# e_book_reader.net
KiCad netlist of a schematic drawn in EAGLE
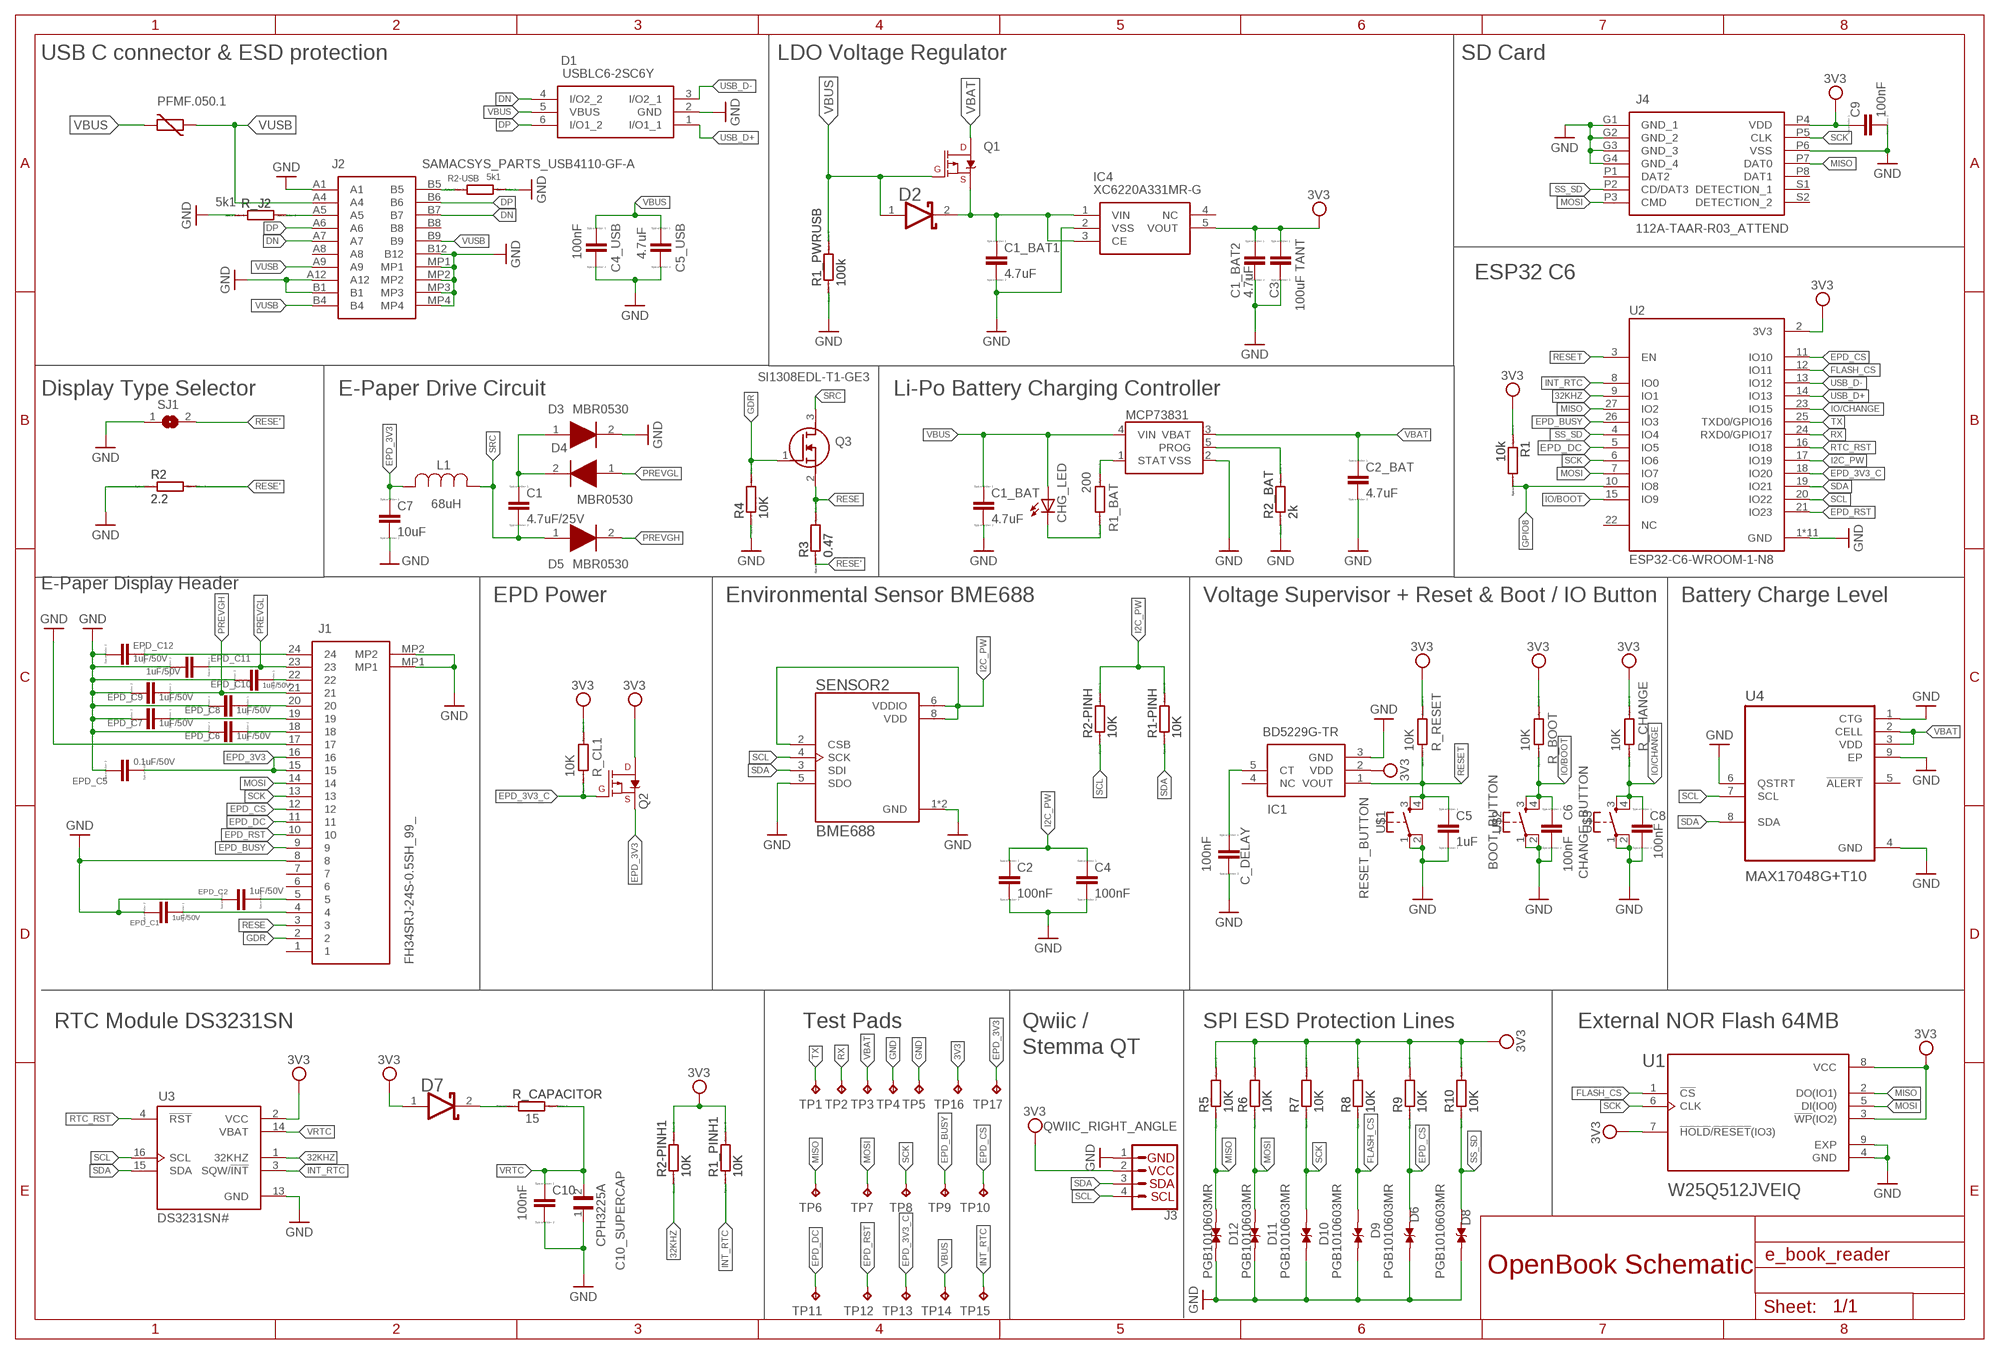
[diagram p0: schematic, sheet 1]

(export (version "E")
  (design (tool "Eeschema 10.0.6"))
  (components
    (comp (ref "C1")
      (value "4.7uF/25V")
      (footprint "eagle-import:ESP32_WROVER_EAGLE-LTSPICE_C0402")
      (libsource (lib "eagle-import") (part "ESP32_WROVER_EAGLE-LTSPICE_C"))
    )
    (comp (ref "C1_BAT")
      (value "4.7uF")
      (footprint "eagle-import:ESP32_WROVER_EAGLE-LTSPICE_C0402")
      (libsource (lib "eagle-import") (part "ESP32_WROVER_EAGLE-LTSPICE_C"))
    )
    (comp (ref "C1_BAT1")
      (value "4.7uF")
      (footprint "eagle-import:ESP32_WROVER_EAGLE-LTSPICE_C0402")
      (libsource (lib "eagle-import") (part "ESP32_WROVER_EAGLE-LTSPICE_C"))
    )
    (comp (ref "C1_BAT2")
      (value "4.7uF")
      (footprint "eagle-import:ESP32_WROVER_EAGLE-LTSPICE_C0402")
      (libsource (lib "eagle-import") (part "ESP32_WROVER_EAGLE-LTSPICE_C"))
    )
    (comp (ref "C2")
      (value "100nF")
      (footprint "eagle-import:ESP32_WROVER_EAGLE-LTSPICE_C0402")
      (libsource (lib "eagle-import") (part "ESP32_WROVER_EAGLE-LTSPICE_C"))
    )
    (comp (ref "C2_BAT")
      (value "4.7uF")
      (footprint "eagle-import:ESP32_WROVER_EAGLE-LTSPICE_C0402")
      (libsource (lib "eagle-import") (part "ESP32_WROVER_EAGLE-LTSPICE_C"))
    )
    (comp (ref "C3")
      (value "100uF TANT")
      (footprint "eagle-import:ESP32_WROVER_EAGLE-LTSPICE_C0402")
      (libsource (lib "eagle-import") (part "ESP32_WROVER_EAGLE-LTSPICE_C"))
    )
    (comp (ref "C4")
      (value "100nF")
      (footprint "eagle-import:ESP32_WROVER_EAGLE-LTSPICE_C0402")
      (libsource (lib "eagle-import") (part "ESP32_WROVER_EAGLE-LTSPICE_C"))
    )
    (comp (ref "C4_USB")
      (value "100nF")
      (footprint "eagle-import:ESP32_WROVER_EAGLE-LTSPICE_C0402")
      (libsource (lib "eagle-import") (part "ESP32_WROVER_EAGLE-LTSPICE_C"))
    )
    (comp (ref "C5")
      (value "1uF")
      (footprint "eagle-import:EAGLE-LTSPICE_C0402")
      (libsource (lib "eagle-import") (part "EAGLE-LTSPICE_CC0402"))
    )
    (comp (ref "C5_USB")
      (value "4.7uF")
      (footprint "eagle-import:ESP32_WROVER_EAGLE-LTSPICE_C0402")
      (libsource (lib "eagle-import") (part "ESP32_WROVER_EAGLE-LTSPICE_C"))
    )
    (comp (ref "C6")
      (value "100nF")
      (footprint "eagle-import:EAGLE-LTSPICE_C0402")
      (libsource (lib "eagle-import") (part "EAGLE-LTSPICE_CC0402"))
    )
    (comp (ref "C7")
      (value "10uF")
      (footprint "eagle-import:ESP32_WROVER_EAGLE-LTSPICE_C0402")
      (libsource (lib "eagle-import") (part "ESP32_WROVER_EAGLE-LTSPICE_C"))
    )
    (comp (ref "C8")
      (value "100nF")
      (footprint "eagle-import:ESP32_WROVER_EAGLE-LTSPICE_C0402")
      (libsource (lib "eagle-import") (part "ESP32_WROVER_EAGLE-LTSPICE_C"))
    )
    (comp (ref "C9")
      (value "100nF")
      (footprint "eagle-import:ESP32_WROVER_EAGLE-LTSPICE_C0402")
      (libsource (lib "eagle-import") (part "ESP32_WROVER_EAGLE-LTSPICE_C"))
    )
    (comp (ref "C10")
      (value "100nF")
      (footprint "eagle-import:ESP32_WROVER_EAGLE-LTSPICE_C0402")
      (libsource (lib "eagle-import") (part "ESP32_WROVER_EAGLE-LTSPICE_C"))
    )
    (comp (ref "C10_SUPERCAP")
      (value "CPH3225A")
      (footprint "eagle-import:CAPCP3225X100N")
      (fields (field (name "MF") "Seiko Instruments"))
      (libsource (lib "eagle-import") (part "CPH3225A"))
    )
    (comp (ref "CHG_LED")
      (value "ADAFRUIT_LEDCHIP-LED0603")
      (footprint "eagle-import:ADAFRUIT_CHIP-LED0603")
      (libsource (lib "eagle-import") (part "ADAFRUIT_LEDCHIP-LED0603"))
    )
    (comp (ref "C_DELAY")
      (value "100nF")
      (footprint "eagle-import:ESP32_WROVER_EAGLE-LTSPICE_C0402")
      (libsource (lib "eagle-import") (part "ESP32_WROVER_EAGLE-LTSPICE_C"))
    )
    (comp (ref "D1")
      (value "USBLC6-2SC6Y")
      (footprint "eagle-import:SOT95P280X145-6N")
      (fields (field (name "MF") "STMicroelectronics"))
      (libsource (lib "eagle-import") (part "USBLC6-2SC6Y"))
    )
    (comp (ref "D2")
      (value "ESP32_WROVER_AVX---SD0805S020S1R0_AVX_SD0805S020S1R0_0_0")
      (footprint "eagle-import:ESP32_WROVER_AVX---SD0805S020S1R0_AVX_SD0805S020S1R0_0")
      (libsource (lib "eagle-import") (part "ESP32_WROVER_AVX---SD0805S020S1R0_AVX_SD0805S020S1R0_0_0"))
    )
    (comp (ref "D3")
      (value "MBR0530")
      (footprint "eagle-import:SOD3716X135N")
      (libsource (lib "eagle-import") (part "MBR0530MY_MBR"))
    )
    (comp (ref "D4")
      (value "MBR0530")
      (footprint "eagle-import:SOD3716X135N")
      (libsource (lib "eagle-import") (part "MBR0530MY_MBR"))
    )
    (comp (ref "D5")
      (value "MBR0530")
      (footprint "eagle-import:SOD3716X135N")
      (libsource (lib "eagle-import") (part "MBR0530MY_MBR"))
    )
    (comp (ref "D6")
      (value "PGB1010603MR")
      (footprint "eagle-import:DIOC1608X36N")
      (libsource (lib "eagle-import") (part "PGB1010603MRPGB1010603MR"))
    )
    (comp (ref "D7")
      (value "ESP32_WROVER_AVX---SD0805S020S1R0_AVX_SD0805S020S1R0_0_0")
      (footprint "eagle-import:ESP32_WROVER_AVX---SD0805S020S1R0_AVX_SD0805S020S1R0_0")
      (libsource (lib "eagle-import") (part "ESP32_WROVER_AVX---SD0805S020S1R0_AVX_SD0805S020S1R0_0_0"))
    )
    (comp (ref "D8")
      (value "PGB1010603MR")
      (footprint "eagle-import:DIOC1608X36N")
      (libsource (lib "eagle-import") (part "PGB1010603MRPGB1010603MR"))
    )
    (comp (ref "D9")
      (value "PGB1010603MR")
      (footprint "eagle-import:DIOC1608X36N")
      (libsource (lib "eagle-import") (part "PGB1010603MRPGB1010603MR"))
    )
    (comp (ref "D10")
      (value "PGB1010603MR")
      (footprint "eagle-import:DIOC1608X36N")
      (libsource (lib "eagle-import") (part "PGB1010603MRPGB1010603MR"))
    )
    (comp (ref "D11")
      (value "PGB1010603MR")
      (footprint "eagle-import:DIOC1608X36N")
      (libsource (lib "eagle-import") (part "PGB1010603MRPGB1010603MR"))
    )
    (comp (ref "D12")
      (value "PGB1010603MR")
      (footprint "eagle-import:DIOC1608X36N")
      (libsource (lib "eagle-import") (part "PGB1010603MRPGB1010603MR"))
    )
    (comp (ref "EPD_C1")
      (value "1uF/50V")
      (footprint "eagle-import:ESP32_WROVER_EAGLE-LTSPICE_C0402")
      (libsource (lib "eagle-import") (part "ESP32_WROVER_EAGLE-LTSPICE_C"))
    )
    (comp (ref "EPD_C2")
      (value "1uF/50V")
      (footprint "eagle-import:ESP32_WROVER_EAGLE-LTSPICE_C0402")
      (libsource (lib "eagle-import") (part "ESP32_WROVER_EAGLE-LTSPICE_C"))
    )
    (comp (ref "EPD_C5")
      (value "0.1uF/50V")
      (footprint "eagle-import:ESP32_WROVER_EAGLE-LTSPICE_C0402")
      (libsource (lib "eagle-import") (part "ESP32_WROVER_EAGLE-LTSPICE_C"))
    )
    (comp (ref "EPD_C6")
      (value "1uF/50V")
      (footprint "eagle-import:ESP32_WROVER_EAGLE-LTSPICE_C0402")
      (libsource (lib "eagle-import") (part "ESP32_WROVER_EAGLE-LTSPICE_C"))
    )
    (comp (ref "EPD_C7")
      (value "1uF/50V")
      (footprint "eagle-import:ESP32_WROVER_EAGLE-LTSPICE_C0402")
      (libsource (lib "eagle-import") (part "ESP32_WROVER_EAGLE-LTSPICE_C"))
    )
    (comp (ref "EPD_C8")
      (value "1uF/50V")
      (footprint "eagle-import:ESP32_WROVER_EAGLE-LTSPICE_C0402")
      (libsource (lib "eagle-import") (part "ESP32_WROVER_EAGLE-LTSPICE_C"))
    )
    (comp (ref "EPD_C9")
      (value "1uF/50V")
      (footprint "eagle-import:ESP32_WROVER_EAGLE-LTSPICE_C0402")
      (libsource (lib "eagle-import") (part "ESP32_WROVER_EAGLE-LTSPICE_C"))
    )
    (comp (ref "EPD_C10")
      (value "1uF/50V")
      (footprint "eagle-import:ESP32_WROVER_EAGLE-LTSPICE_C0402")
      (libsource (lib "eagle-import") (part "ESP32_WROVER_EAGLE-LTSPICE_C"))
    )
    (comp (ref "EPD_C11")
      (value "1uF/50V")
      (footprint "eagle-import:ESP32_WROVER_EAGLE-LTSPICE_C0402")
      (libsource (lib "eagle-import") (part "ESP32_WROVER_EAGLE-LTSPICE_C"))
    )
    (comp (ref "EPD_C12")
      (value "1uF/50V")
      (footprint "eagle-import:ESP32_WROVER_EAGLE-LTSPICE_C0402")
      (libsource (lib "eagle-import") (part "ESP32_WROVER_EAGLE-LTSPICE_C"))
    )
    (comp (ref "IC1")
      (value "BD5229G-TR")
      (footprint "eagle-import:SOT95P280X125-5N")
      (fields (field (name "MOUSER_PART_NUMBER") "755-BD5229G-TR"))
      (libsource (lib "eagle-import") (part "BD5229G-TR"))
    )
    (comp (ref "IC4")
      (value "XC6220A331MR-G")
      (footprint "eagle-import:SOT95P280X120-5N")
      (fields (field (name "MOUSER_PART_NUMBER") "865-XC6220A331MR-G"))
      (libsource (lib "eagle-import") (part "XC6220A331MR-G"))
    )
    (comp (ref "J1")
      (value "FH34SRJ-24S-0.5SH_99_")
      (footprint "eagle-import:FH34SRJ24S05SH99")
      (fields
        (field (name "MANUFACTURER_PART_NUMBER") "FH34SRJ-24S-0.5SH(99)")
        (field (name "MOUSER_PART_NUMBER") "798-FH34SRJ24S05SH99")
      )
      (libsource (lib "eagle-import") (part "FH34SRJ-24S-0.5SH_99_"))
    )
    (comp (ref "J2")
      (value "SAMACSYS_PARTS_USB4110-GF-A")
      (footprint "eagle-import:SAMACSYS_PARTS_USB4110GFA")
      (fields
        (field (name "MANUFACTURER_PART_NUMBER") "USB4110-GF-A")
        (field (name "MOUSER_PART_NUMBER") "640-USB4110-GF-A")
      )
      (libsource (lib "eagle-import") (part "SAMACSYS_PARTS_USB4110-GF-A"))
    )
    (comp (ref "J3")
      (value "QWIIC_RIGHT_ANGLE")
      (footprint "eagle-import:JST04_1MM_RA")
      (libsource (lib "eagle-import") (part "QWIIC_CONNECTORJS-1MM"))
    )
    (comp (ref "J4")
      (value "112A-TAAR-R03_ATTEND")
      (footprint "eagle-import:112ATAARR03ATTEND")
      (fields (field (name "MANUFACTURER_PART_NUMBER") "112A-TAAR-R03 ATTEND"))
      (libsource (lib "eagle-import") (part "112A-TAAR-R03_ATTEND"))
    )
    (comp (ref "L1")
      (value "68uH")
      (footprint "eagle-import:IND_4828-WE-TPC_WRE")
      (fields
        (field (name "MANUFACTURER_PART_NUMBER") "744043680")
        (field (name "COPYRIGHT") "Copyright (C) 2024 Ultra Librarian. All rights reserved.")
      )
      (libsource (lib "eagle-import") (part "744043680IND_4828-WE-TPC_WRE"))
    )
    (comp (ref "MCP73831")
      (value "ESP32_WROVER_SPARKFUN-IC-POWER_MCP73831")
      (footprint "eagle-import:ESP32_WROVER_SPARKFUN-IC-POWER_SOT23-5")
      (libsource (lib "eagle-import") (part "ESP32_WROVER_SPARKFUN-IC-POWER_MCP73831"))
    )
    (comp (ref "PFMF.050.1")
      (value "ESP32C6_VARISTORCN1812")
      (footprint "eagle-import:ESP32C6_VARISTOR_CT_CN1812")
      (libsource (lib "eagle-import") (part "ESP32C6_VARISTORCN1812"))
    )
    (comp (ref "Q1")
      (value "ESP32_WROVER_SPARKFUN-DISCRETESEMI_MOSFET_PCH")
      (footprint "eagle-import:ESP32_WROVER_SPARKFUN-DISCRETESEMI_SOT23-3")
      (libsource (lib "eagle-import") (part "ESP32_WROVER_SPARKFUN-DISCRETESEMI_MOSFET_PCH"))
    )
    (comp (ref "Q2")
      (value "ESP32_WROVER_SPARKFUN-DISCRETESEMI_MOSFET_PCH")
      (footprint "eagle-import:ESP32_WROVER_SPARKFUN-DISCRETESEMI_SOT23-3")
      (libsource (lib "eagle-import") (part "ESP32_WROVER_SPARKFUN-DISCRETESEMI_MOSFET_PCH"))
    )
    (comp (ref "Q3")
      (value "SI1308EDL-T1-GE3")
      (footprint "eagle-import:SOT65P210X110-3N")
      (fields (field (name "MF") "Vishay Siliconix"))
      (libsource (lib "eagle-import") (part "SI1308EDL-T1-GE3"))
    )
    (comp (ref "R1")
      (value "10k")
      (footprint "eagle-import:ESP32_WROVER_EAGLE-LTSPICE_R0402")
      (libsource (lib "eagle-import") (part "ESP32_WROVER_EAGLE-LTSPICE_R"))
    )
    (comp (ref "R1-PINH")
      (value "10K")
      (footprint "eagle-import:ESP32_WROVER_EAGLE-LTSPICE_R0402")
      (libsource (lib "eagle-import") (part "ESP32_WROVER_EAGLE-LTSPICE_R"))
    )
    (comp (ref "R1_BAT")
      (value "200")
      (footprint "eagle-import:ESP32_WROVER_EAGLE-LTSPICE_R0402")
      (libsource (lib "eagle-import") (part "ESP32_WROVER_EAGLE-LTSPICE_R"))
    )
    (comp (ref "R1_PINH1")
      (value "10K")
      (footprint "eagle-import:ESP32_WROVER_EAGLE-LTSPICE_R0402")
      (libsource (lib "eagle-import") (part "ESP32_WROVER_EAGLE-LTSPICE_R"))
    )
    (comp (ref "R1_PWRUSB")
      (value "100k")
      (footprint "eagle-import:ESP32_WROVER_EAGLE-LTSPICE_R0402")
      (libsource (lib "eagle-import") (part "ESP32_WROVER_EAGLE-LTSPICE_R"))
    )
    (comp (ref "R2")
      (value "2.2")
      (footprint "eagle-import:ESP32_WROVER_EAGLE-LTSPICE_R0402")
      (libsource (lib "eagle-import") (part "ESP32_WROVER_EAGLE-LTSPICE_R"))
    )
    (comp (ref "R2-PINH")
      (value "10K")
      (footprint "eagle-import:ESP32_WROVER_EAGLE-LTSPICE_R0402")
      (libsource (lib "eagle-import") (part "ESP32_WROVER_EAGLE-LTSPICE_R"))
    )
    (comp (ref "R2-PINH1")
      (value "10K")
      (footprint "eagle-import:ESP32_WROVER_EAGLE-LTSPICE_R0402")
      (libsource (lib "eagle-import") (part "ESP32_WROVER_EAGLE-LTSPICE_R"))
    )
    (comp (ref "R2-USB")
      (value "5k1")
      (footprint "eagle-import:ESP32_WROVER_EAGLE-LTSPICE_R0402")
      (libsource (lib "eagle-import") (part "ESP32_WROVER_EAGLE-LTSPICE_R"))
    )
    (comp (ref "R2_BAT")
      (value "2k")
      (footprint "eagle-import:ESP32_WROVER_EAGLE-LTSPICE_R0402")
      (libsource (lib "eagle-import") (part "ESP32_WROVER_EAGLE-LTSPICE_R"))
    )
    (comp (ref "R3")
      (value "0.47")
      (footprint "eagle-import:ESP32_WROVER_EAGLE-LTSPICE_R0402")
      (libsource (lib "eagle-import") (part "ESP32_WROVER_EAGLE-LTSPICE_R"))
    )
    (comp (ref "R4")
      (value "10K")
      (footprint "eagle-import:ESP32_WROVER_EAGLE-LTSPICE_R0402")
      (libsource (lib "eagle-import") (part "ESP32_WROVER_EAGLE-LTSPICE_R"))
    )
    (comp (ref "R5")
      (value "10K")
      (footprint "eagle-import:ESP32_WROVER_EAGLE-LTSPICE_R0402")
      (libsource (lib "eagle-import") (part "ESP32_WROVER_EAGLE-LTSPICE_R"))
    )
    (comp (ref "R6")
      (value "10K")
      (footprint "eagle-import:ESP32_WROVER_EAGLE-LTSPICE_R0402")
      (libsource (lib "eagle-import") (part "ESP32_WROVER_EAGLE-LTSPICE_R"))
    )
    (comp (ref "R7")
      (value "10K")
      (footprint "eagle-import:ESP32_WROVER_EAGLE-LTSPICE_R0402")
      (libsource (lib "eagle-import") (part "ESP32_WROVER_EAGLE-LTSPICE_R"))
    )
    (comp (ref "R8")
      (value "10K")
      (footprint "eagle-import:ESP32_WROVER_EAGLE-LTSPICE_R0402")
      (libsource (lib "eagle-import") (part "ESP32_WROVER_EAGLE-LTSPICE_R"))
    )
    (comp (ref "R9")
      (value "10K")
      (footprint "eagle-import:ESP32_WROVER_EAGLE-LTSPICE_R0402")
      (libsource (lib "eagle-import") (part "ESP32_WROVER_EAGLE-LTSPICE_R"))
    )
    (comp (ref "R10")
      (value "10K")
      (footprint "eagle-import:ESP32_WROVER_EAGLE-LTSPICE_R0402")
      (libsource (lib "eagle-import") (part "ESP32_WROVER_EAGLE-LTSPICE_R"))
    )
    (comp (ref "R_BOOT")
      (value "10K")
      (footprint "eagle-import:ESP32_WROVER_EAGLE-LTSPICE_R0402")
      (libsource (lib "eagle-import") (part "ESP32_WROVER_EAGLE-LTSPICE_R"))
    )
    (comp (ref "R_CAPACITOR")
      (value "15")
      (footprint "eagle-import:ESP32_WROVER_EAGLE-LTSPICE_R0402")
      (libsource (lib "eagle-import") (part "ESP32_WROVER_EAGLE-LTSPICE_R"))
    )
    (comp (ref "R_CHANGE")
      (value "10K")
      (footprint "eagle-import:ESP32_WROVER_EAGLE-LTSPICE_R0402")
      (libsource (lib "eagle-import") (part "ESP32_WROVER_EAGLE-LTSPICE_R"))
    )
    (comp (ref "R_CL1")
      (value "10K")
      (footprint "eagle-import:ESP32_WROVER_EAGLE-LTSPICE_R0402")
      (libsource (lib "eagle-import") (part "ESP32_WROVER_EAGLE-LTSPICE_R"))
    )
    (comp (ref "R_J2")
      (value "5k1")
      (footprint "eagle-import:ESP32_WROVER_EAGLE-LTSPICE_R0402")
      (libsource (lib "eagle-import") (part "ESP32_WROVER_EAGLE-LTSPICE_R"))
    )
    (comp (ref "R_RESET")
      (value "10K")
      (footprint "eagle-import:ESP32_WROVER_EAGLE-LTSPICE_R0402")
      (libsource (lib "eagle-import") (part "ESP32_WROVER_EAGLE-LTSPICE_R"))
    )
    (comp (ref "SENSOR2")
      (value "BME688")
      (footprint "eagle-import:ESP32_WROVER_BME680_PSON80P300X300X100-8N")
      (fields (field (name "MF") "Bosch Sensortec") (field (name "MP") "BME680"))
      (libsource (lib "eagle-import") (part "ESP32_WROVER_BME680_BME680"))
    )
    (comp (ref "SJ1") (value "SJ") (footprint "eagle-import:SJ") (libsource (lib "eagle-import") (part "SJ")))
    (comp (ref "TP1")
      (value "TPTP20R")
      (footprint "eagle-import:TP20R")
      (libsource (lib "eagle-import") (part "TPTP20R"))
    )
    (comp (ref "TP2")
      (value "TPTP20R")
      (footprint "eagle-import:TP20R")
      (libsource (lib "eagle-import") (part "TPTP20R"))
    )
    (comp (ref "TP3")
      (value "TPTP20R")
      (footprint "eagle-import:TP20R")
      (libsource (lib "eagle-import") (part "TPTP20R"))
    )
    (comp (ref "TP4")
      (value "TPTP20R")
      (footprint "eagle-import:TP20R")
      (libsource (lib "eagle-import") (part "TPTP20R"))
    )
    (comp (ref "TP5")
      (value "TPTP20R")
      (footprint "eagle-import:TP20R")
      (libsource (lib "eagle-import") (part "TPTP20R"))
    )
    (comp (ref "TP6")
      (value "TPTP20R")
      (footprint "eagle-import:TP20R")
      (libsource (lib "eagle-import") (part "TPTP20R"))
    )
    (comp (ref "TP7")
      (value "TPTP20R")
      (footprint "eagle-import:TP20R")
      (libsource (lib "eagle-import") (part "TPTP20R"))
    )
    (comp (ref "TP8")
      (value "TPTP20R")
      (footprint "eagle-import:TP20R")
      (libsource (lib "eagle-import") (part "TPTP20R"))
    )
    (comp (ref "TP9")
      (value "TPTP20R")
      (footprint "eagle-import:TP20R")
      (libsource (lib "eagle-import") (part "TPTP20R"))
    )
    (comp (ref "TP10")
      (value "TPTP20R")
      (footprint "eagle-import:TP20R")
      (libsource (lib "eagle-import") (part "TPTP20R"))
    )
    (comp (ref "TP11")
      (value "TPTP20R")
      (footprint "eagle-import:TP20R")
      (libsource (lib "eagle-import") (part "TPTP20R"))
    )
    (comp (ref "TP12")
      (value "TPTP20R")
      (footprint "eagle-import:TP20R")
      (libsource (lib "eagle-import") (part "TPTP20R"))
    )
    (comp (ref "TP13")
      (value "TPTP20R")
      (footprint "eagle-import:TP20R")
      (libsource (lib "eagle-import") (part "TPTP20R"))
    )
    (comp (ref "TP14")
      (value "TPTP20R")
      (footprint "eagle-import:TP20R")
      (libsource (lib "eagle-import") (part "TPTP20R"))
    )
    (comp (ref "TP15")
      (value "TPTP20R")
      (footprint "eagle-import:TP20R")
      (libsource (lib "eagle-import") (part "TPTP20R"))
    )
    (comp (ref "TP16")
      (value "TPTP20R")
      (footprint "eagle-import:TP20R")
      (libsource (lib "eagle-import") (part "TPTP20R"))
    )
    (comp (ref "TP17")
      (value "TP")
      (footprint "eagle-import:TP20R")
      (libsource (lib "eagle-import") (part "TP"))
    )
    (comp (ref "U$1")
      (value "RESET_BUTTON")
      (footprint "eagle-import:MYBUTTON")
      (libsource (lib "eagle-import") (part "BUTTON_CUSYOMV12_MYBUTTON"))
    )
    (comp (ref "U$2")
      (value "BOOT_BUTTON")
      (footprint "eagle-import:MYBUTTON")
      (libsource (lib "eagle-import") (part "BUTTON_CUSYOMV12_MYBUTTON"))
    )
    (comp (ref "U$3")
      (value "CHANGE_BUTTON")
      (footprint "eagle-import:MYBUTTON")
      (libsource (lib "eagle-import") (part "BUTTON_CUSYOMV12_MYBUTTON"))
    )
    (comp (ref "U1")
      (value "W25Q512JVEIQ")
      (footprint "eagle-import:SON127P600X800X80-9N")
      (fields (field (name "MF") "Winbond Electronics"))
      (libsource (lib "eagle-import") (part "W25Q512JVEIQ"))
    )
    (comp (ref "U2")
      (value "ESP32-C6-WROOM-1-N8")
      (footprint "eagle-import:XCVR_ESP32-C6-WROOM-1-N8")
      (fields (field (name "MF") "Espressif Systems"))
      (libsource (lib "eagle-import") (part "ESP32-C6-WROOM-1-N8"))
    )
    (comp (ref "U3")
      (value "DS3231SN#")
      (footprint "eagle-import:SOIC127P1032X265-16N")
      (fields (field (name "MF") "Analog Devices"))
      (libsource (lib "eagle-import") (part "DS3231SN#"))
    )
    (comp (ref "U4")
      (value "MAX17048G+T10")
      (footprint "eagle-import:SON50P200X200X80-9N")
      (fields (field (name "MF") "Analog Devices"))
      (libsource (lib "eagle-import") (part "MAX17048G+T10"))
    )
  )
  (nets
    (net (code "1") (name "3V3") (class "Default")
      (node (ref "C1_BAT2") (pin "1") (pinfunction "1_1") (pintype "passive"))
      (node (ref "C3") (pin "1") (pinfunction "1_1") (pintype "passive"))
      (node (ref "C9") (pin "1") (pinfunction "1_1") (pintype "passive"))
      (node (ref "D7") (pin "1") (pinfunction "ANODE_1") (pintype "bidirectional"))
      (node (ref "IC1") (pin "2") (pinfunction "VDD_2") (pintype "bidirectional"))
      (node (ref "IC4") (pin "5") (pinfunction "VOUT_5") (pintype "bidirectional"))
      (node (ref "J3") (pin "2") (pinfunction "2_2") (pintype "power_in"))
      (node (ref "J4") (pin "P4") (pinfunction "VDD_P4") (pintype "bidirectional"))
      (node (ref "Q2") (pin "1") (pinfunction "D_1") (pintype "bidirectional"))
      (node (ref "R1") (pin "1") (pinfunction "1_1") (pintype "passive"))
      (node (ref "R10") (pin "2") (pinfunction "2_2") (pintype "passive"))
      (node (ref "R1_PINH1") (pin "2") (pinfunction "2_2") (pintype "passive"))
      (node (ref "R2-PINH1") (pin "2") (pinfunction "2_2") (pintype "passive"))
      (node (ref "R5") (pin "2") (pinfunction "2_2") (pintype "passive"))
      (node (ref "R6") (pin "2") (pinfunction "2_2") (pintype "passive"))
      (node (ref "R7") (pin "2") (pinfunction "2_2") (pintype "passive"))
      (node (ref "R8") (pin "2") (pinfunction "2_2") (pintype "passive"))
      (node (ref "R9") (pin "2") (pinfunction "2_2") (pintype "passive"))
      (node (ref "R_BOOT") (pin "2") (pinfunction "2_2") (pintype "passive"))
      (node (ref "R_CHANGE") (pin "2") (pinfunction "2_2") (pintype "passive"))
      (node (ref "R_CL1") (pin "2") (pinfunction "2_2") (pintype "passive"))
      (node (ref "R_RESET") (pin "2") (pinfunction "2_2") (pintype "passive"))
      (node (ref "TP16") (pin "TP") (pinfunction "TP_TP") (pintype "input"))
      (node (ref "U1") (pin "3") (pinfunction "~{WP}(IO2)_3") (pintype "bidirectional"))
      (node (ref "U1") (pin "7") (pinfunction "~{HOLD}/~{RESET}(IO3)_7") (pintype "bidirectional"))
      (node (ref "U1") (pin "8") (pinfunction "VCC_8") (pintype "power_in"))
      (node (ref "U2") (pin "2") (pinfunction "3V3_2") (pintype "power_in"))
      (node (ref "U3") (pin "2") (pinfunction "VCC_2") (pintype "power_in"))
    )
    (net (code "2") (name "32KHZ") (class "Default")
      (node (ref "R2-PINH1") (pin "1") (pinfunction "1_1") (pintype "passive"))
      (node (ref "U2") (pin "9") (pinfunction "IO1_9") (pintype "bidirectional"))
      (node (ref "U3") (pin "1") (pinfunction "32KHZ_1") (pintype "output"))
    )
    (net (code "3") (name "DN") (class "Default")
      (node (ref "D1") (pin "4") (pinfunction "I/O2_2_4") (pintype "bidirectional"))
      (node (ref "J2") (pin "A7") (pinfunction "A7_A7") (pintype "bidirectional"))
      (node (ref "J2") (pin "B7") (pinfunction "B7_B7") (pintype "bidirectional"))
    )
    (net (code "4") (name "DP") (class "Default")
      (node (ref "D1") (pin "6") (pinfunction "I/O1_2_6") (pintype "bidirectional"))
      (node (ref "J2") (pin "A6") (pinfunction "A6_A6") (pintype "bidirectional"))
      (node (ref "J2") (pin "B6") (pinfunction "B6_B6") (pintype "bidirectional"))
    )
    (net (code "5") (name "EPD_3V3") (class "Default")
      (node (ref "C7") (pin "1") (pinfunction "1_1") (pintype "passive"))
      (node (ref "EPD_C5") (pin "1") (pinfunction "1_1") (pintype "passive"))
      (node (ref "J1") (pin "15") (pinfunction "15_15") (pintype "bidirectional"))
      (node (ref "J1") (pin "16") (pinfunction "16_16") (pintype "bidirectional"))
      (node (ref "L1") (pin "2") (pinfunction "2_2") (pintype "passive"))
      (node (ref "Q2") (pin "3") (pinfunction "S_3") (pintype "bidirectional"))
      (node (ref "TP17") (pin "TP") (pinfunction "TP_TP") (pintype "input"))
    )
    (net (code "6") (name "EPD_3V3_C") (class "Default")
      (node (ref "Q2") (pin "2") (pinfunction "G_2") (pintype "bidirectional"))
      (node (ref "R_CL1") (pin "1") (pinfunction "1_1") (pintype "passive"))
      (node (ref "TP13") (pin "TP") (pinfunction "TP_TP") (pintype "input"))
      (node (ref "U2") (pin "18") (pinfunction "IO20_18") (pintype "bidirectional"))
    )
    (net (code "7") (name "EPD_BUSY") (class "Default")
      (node (ref "J1") (pin "9") (pinfunction "9_9") (pintype "bidirectional"))
      (node (ref "TP9") (pin "TP") (pinfunction "TP_TP") (pintype "input"))
      (node (ref "U2") (pin "26") (pinfunction "IO3_26") (pintype "bidirectional"))
    )
    (net (code "8") (name "EPD_CS") (class "Default")
      (node (ref "D6") (pin "1") (pinfunction "1_1") (pintype "passive"))
      (node (ref "J1") (pin "12") (pinfunction "12_12") (pintype "bidirectional"))
      (node (ref "R9") (pin "1") (pinfunction "1_1") (pintype "passive"))
      (node (ref "TP10") (pin "TP") (pinfunction "TP_TP") (pintype "input"))
      (node (ref "U2") (pin "11") (pinfunction "IO10_11") (pintype "bidirectional"))
    )
    (net (code "9") (name "EPD_DC") (class "Default")
      (node (ref "J1") (pin "11") (pinfunction "11_11") (pintype "bidirectional"))
      (node (ref "TP11") (pin "TP") (pinfunction "TP_TP") (pintype "input"))
      (node (ref "U2") (pin "5") (pinfunction "IO5_5") (pintype "bidirectional"))
    )
    (net (code "10") (name "EPD_RST") (class "Default")
      (node (ref "J1") (pin "10") (pinfunction "10_10") (pintype "bidirectional"))
      (node (ref "TP12") (pin "TP") (pinfunction "TP_TP") (pintype "input"))
      (node (ref "U2") (pin "21") (pinfunction "IO23_21") (pintype "bidirectional"))
    )
    (net (code "11") (name "FLASH_CS") (class "Default")
      (node (ref "D9") (pin "1") (pinfunction "1_1") (pintype "passive"))
      (node (ref "R8") (pin "1") (pinfunction "1_1") (pintype "passive"))
      (node (ref "U1") (pin "1") (pinfunction "~{CS}_1") (pintype "input"))
      (node (ref "U2") (pin "12") (pinfunction "IO11_12") (pintype "bidirectional"))
    )
    (net (code "12") (name "GDR") (class "Default")
      (node (ref "J1") (pin "2") (pinfunction "2_2") (pintype "bidirectional"))
      (node (ref "Q3") (pin "1") (pinfunction "G_1") (pintype "bidirectional"))
      (node (ref "R4") (pin "2") (pinfunction "2_2") (pintype "passive"))
    )
    (net (code "13") (name "GND") (class "Default")
      (node (ref "C10") (pin "2") (pinfunction "2_2") (pintype "passive"))
      (node (ref "C10_SUPERCAP") (pin "1") (pinfunction "1_1") (pintype "passive"))
      (node (ref "C1_BAT") (pin "2") (pinfunction "2_2") (pintype "passive"))
      (node (ref "C1_BAT1") (pin "2") (pinfunction "2_2") (pintype "passive"))
      (node (ref "C1_BAT2") (pin "2") (pinfunction "2_2") (pintype "passive"))
      (node (ref "C2") (pin "2") (pinfunction "2_2") (pintype "passive"))
      (node (ref "C2_BAT") (pin "2") (pinfunction "2_2") (pintype "passive"))
      (node (ref "C3") (pin "2") (pinfunction "2_2") (pintype "passive"))
      (node (ref "C4") (pin "2") (pinfunction "2_2") (pintype "passive"))
      (node (ref "C4_USB") (pin "2") (pinfunction "2_2") (pintype "passive"))
      (node (ref "C5") (pin "2") (pinfunction "2_2") (pintype "passive"))
      (node (ref "C5_USB") (pin "2") (pinfunction "2_2") (pintype "passive"))
      (node (ref "C6") (pin "2") (pinfunction "2_2") (pintype "passive"))
      (node (ref "C7") (pin "2") (pinfunction "2_2") (pintype "passive"))
      (node (ref "C8") (pin "2") (pinfunction "2_2") (pintype "passive"))
      (node (ref "C9") (pin "2") (pinfunction "2_2") (pintype "passive"))
      (node (ref "C_DELAY") (pin "2") (pinfunction "2_2") (pintype "passive"))
      (node (ref "D1") (pin "2") (pinfunction "GND_2") (pintype "bidirectional"))
      (node (ref "D10") (pin "2") (pinfunction "2_2") (pintype "passive"))
      (node (ref "D11") (pin "2") (pinfunction "2_2") (pintype "passive"))
      (node (ref "D12") (pin "2") (pinfunction "2_2") (pintype "passive"))
      (node (ref "D3") (pin "2") (pinfunction "K_2") (pintype "bidirectional"))
      (node (ref "D6") (pin "2") (pinfunction "2_2") (pintype "passive"))
      (node (ref "D8") (pin "2") (pinfunction "2_2") (pintype "passive"))
      (node (ref "D9") (pin "2") (pinfunction "2_2") (pintype "passive"))
      (node (ref "EPD_C1") (pin "2") (pinfunction "2_2") (pintype "passive"))
      (node (ref "EPD_C10") (pin "2") (pinfunction "2_2") (pintype "passive"))
      (node (ref "EPD_C11") (pin "2") (pinfunction "2_2") (pintype "passive"))
      (node (ref "EPD_C12") (pin "2") (pinfunction "2_2") (pintype "passive"))
      (node (ref "EPD_C2") (pin "2") (pinfunction "2_2") (pintype "passive"))
      (node (ref "EPD_C5") (pin "2") (pinfunction "2_2") (pintype "passive"))
      (node (ref "EPD_C6") (pin "2") (pinfunction "2_2") (pintype "passive"))
      (node (ref "EPD_C7") (pin "2") (pinfunction "2_2") (pintype "passive"))
      (node (ref "EPD_C8") (pin "2") (pinfunction "2_2") (pintype "passive"))
      (node (ref "EPD_C9") (pin "2") (pinfunction "2_2") (pintype "passive"))
      (node (ref "IC1") (pin "3") (pinfunction "GND_3") (pintype "bidirectional"))
      (node (ref "IC4") (pin "2") (pinfunction "VSS_2") (pintype "bidirectional"))
      (node (ref "J1") (pin "17") (pinfunction "17_17") (pintype "bidirectional"))
      (node (ref "J1") (pin "8") (pinfunction "8_8") (pintype "bidirectional"))
      (node (ref "J1") (pin "MP1") (pinfunction "MP1_MP1") (pintype "bidirectional"))
      (node (ref "J1") (pin "MP2") (pinfunction "MP2_MP2") (pintype "bidirectional"))
      (node (ref "J2") (pin "A1") (pinfunction "A1_A1") (pintype "bidirectional"))
      (node (ref "J2") (pin "A12") (pinfunction "A12_A12") (pintype "bidirectional"))
      (node (ref "J2") (pin "B1") (pinfunction "B1_B1") (pintype "bidirectional"))
      (node (ref "J2") (pin "B12") (pinfunction "B12_B12") (pintype "bidirectional"))
      (node (ref "J2") (pin "MP1") (pinfunction "MP1_MP1") (pintype "bidirectional"))
      (node (ref "J2") (pin "MP2") (pinfunction "MP2_MP2") (pintype "bidirectional"))
      (node (ref "J2") (pin "MP3") (pinfunction "MP3_MP3") (pintype "bidirectional"))
      (node (ref "J2") (pin "MP4") (pinfunction "MP4_MP4") (pintype "bidirectional"))
      (node (ref "J3") (pin "1") (pinfunction "1_1") (pintype "power_in"))
      (node (ref "J4") (pin "G1") (pinfunction "GND_1_G1") (pintype "bidirectional"))
      (node (ref "J4") (pin "G2") (pinfunction "GND_2_G2") (pintype "bidirectional"))
      (node (ref "J4") (pin "G3") (pinfunction "GND_3_G3") (pintype "bidirectional"))
      (node (ref "J4") (pin "G4") (pinfunction "GND_4_G4") (pintype "bidirectional"))
      (node (ref "J4") (pin "P6") (pinfunction "VSS_P6") (pintype "bidirectional"))
      (node (ref "MCP73831") (pin "2") (pinfunction "VSS_2") (pintype "power_in"))
      (node (ref "R1_PWRUSB") (pin "1") (pinfunction "1_1") (pintype "passive"))
      (node (ref "R2") (pin "1") (pinfunction "1_1") (pintype "passive"))
      (node (ref "R2-USB") (pin "2") (pinfunction "2_2") (pintype "passive"))
      (node (ref "R2_BAT") (pin "1") (pinfunction "1_1") (pintype "passive"))
      (node (ref "R4") (pin "1") (pinfunction "1_1") (pintype "passive"))
      (node (ref "R_J2") (pin "1") (pinfunction "1_1") (pintype "passive"))
      (node (ref "SENSOR2") (pin "1") (pinfunction "GND_1") (pintype "power_in"))
      (node (ref "SENSOR2") (pin "5") (pinfunction "SDO_5") (pintype "bidirectional"))
      (node (ref "SENSOR2") (pin "7") (pinfunction "GND_7") (pintype "power_in"))
      (node (ref "SJ1") (pin "1") (pinfunction "1_1") (pintype "passive"))
      (node (ref "TP4") (pin "TP") (pinfunction "TP_TP") (pintype "input"))
      (node (ref "TP5") (pin "TP") (pinfunction "TP_TP") (pintype "input"))
      (node (ref "U$1") (pin "1") (pinfunction "1_1") (pintype "passive"))
      (node (ref "U$1") (pin "2") (pinfunction "2_2") (pintype "passive"))
      (node (ref "U$2") (pin "1") (pinfunction "1_1") (pintype "passive"))
      (node (ref "U$2") (pin "2") (pinfunction "2_2") (pintype "passive"))
      (node (ref "U$3") (pin "1") (pinfunction "1_1") (pintype "passive"))
      (node (ref "U$3") (pin "2") (pinfunction "2_2") (pintype "passive"))
      (node (ref "U1") (pin "4") (pinfunction "GND_4") (pintype "power_in"))
      (node (ref "U1") (pin "9") (pinfunction "EXP_9") (pintype "passive"))
      (node (ref "U2") (pin "1") (pinfunction "GND_1") (pintype "power_in"))
      (node (ref "U2") (pin "28") (pinfunction "GND_28") (pintype "power_in"))
      (node (ref "U2") (pin "29_1") (pinfunction "GND_29_1") (pintype "power_in"))
      (node (ref "U2") (pin "29_2") (pinfunction "GND_29_2") (pintype "power_in"))
      (node (ref "U2") (pin "29_3") (pinfunction "GND_29_3") (pintype "power_in"))
      (node (ref "U2") (pin "29_4") (pinfunction "GND_29_4") (pintype "power_in"))
      (node (ref "U2") (pin "29_5") (pinfunction "GND_29_5") (pintype "power_in"))
      (node (ref "U2") (pin "29_6") (pinfunction "GND_29_6") (pintype "power_in"))
      (node (ref "U2") (pin "29_7") (pinfunction "GND_29_7") (pintype "power_in"))
      (node (ref "U2") (pin "29_8") (pinfunction "GND_29_8") (pintype "power_in"))
      (node (ref "U2") (pin "29_9") (pinfunction "GND_29_9") (pintype "power_in"))
      (node (ref "U3") (pin "13") (pinfunction "GND_13") (pintype "power_in"))
      (node (ref "U4") (pin "1") (pinfunction "CTG_1") (pintype "power_in"))
      (node (ref "U4") (pin "4") (pinfunction "GND_4") (pintype "power_in"))
      (node (ref "U4") (pin "6") (pinfunction "QSTRT_6") (pintype "input"))
      (node (ref "U4") (pin "9") (pinfunction "EP_9") (pintype "power_in"))
    )
    (net (code "14") (name "GPIO8") (class "Default")
      (node (ref "R1") (pin "2") (pinfunction "2_2") (pintype "passive"))
      (node (ref "U2") (pin "10") (pinfunction "IO8_10") (pintype "bidirectional"))
    )
    (net (code "15") (name "I2C_PW") (class "Default")
      (node (ref "C2") (pin "1") (pinfunction "1_1") (pintype "passive"))
      (node (ref "C4") (pin "1") (pinfunction "1_1") (pintype "passive"))
      (node (ref "R1-PINH") (pin "2") (pinfunction "2_2") (pintype "passive"))
      (node (ref "R2-PINH") (pin "2") (pinfunction "2_2") (pintype "passive"))
      (node (ref "SENSOR2") (pin "2") (pinfunction "CSB_2") (pintype "input"))
      (node (ref "SENSOR2") (pin "6") (pinfunction "VDDIO_6") (pintype "power_in"))
      (node (ref "SENSOR2") (pin "8") (pinfunction "VDD_8") (pintype "power_in"))
      (node (ref "U2") (pin "17") (pinfunction "IO19_17") (pintype "bidirectional"))
    )
    (net (code "16") (name "INT_RTC") (class "Default")
      (node (ref "R1_PINH1") (pin "1") (pinfunction "1_1") (pintype "passive"))
      (node (ref "TP15") (pin "TP") (pinfunction "TP_TP") (pintype "input"))
      (node (ref "U2") (pin "8") (pinfunction "IO0_8") (pintype "bidirectional"))
      (node (ref "U3") (pin "3") (pinfunction "SQW/~{INT}_3") (pintype "output"))
    )
    (net (code "17") (name "IO{slash}BOOT") (class "Default")
      (node (ref "C6") (pin "1") (pinfunction "1_1") (pintype "passive"))
      (node (ref "R_BOOT") (pin "1") (pinfunction "1_1") (pintype "passive"))
      (node (ref "U$2") (pin "3") (pinfunction "3_3") (pintype "passive"))
      (node (ref "U$2") (pin "4") (pinfunction "4_4") (pintype "passive"))
      (node (ref "U2") (pin "15") (pinfunction "IO9_15") (pintype "bidirectional"))
    )
    (net (code "18") (name "IO{slash}CHANGE") (class "Default")
      (node (ref "C8") (pin "1") (pinfunction "1_1") (pintype "passive"))
      (node (ref "R_CHANGE") (pin "1") (pinfunction "1_1") (pintype "passive"))
      (node (ref "U$3") (pin "3") (pinfunction "3_3") (pintype "passive"))
      (node (ref "U$3") (pin "4") (pinfunction "4_4") (pintype "passive"))
      (node (ref "U2") (pin "23") (pinfunction "IO15_23") (pintype "bidirectional"))
    )
    (net (code "19") (name "MISO") (class "Default")
      (node (ref "D12") (pin "1") (pinfunction "1_1") (pintype "passive"))
      (node (ref "J4") (pin "P7") (pinfunction "DAT0_P7") (pintype "bidirectional"))
      (node (ref "R5") (pin "1") (pinfunction "1_1") (pintype "passive"))
      (node (ref "TP6") (pin "TP") (pinfunction "TP_TP") (pintype "input"))
      (node (ref "U1") (pin "2") (pinfunction "DO(IO1)_2") (pintype "bidirectional"))
      (node (ref "U2") (pin "27") (pinfunction "IO2_27") (pintype "bidirectional"))
    )
    (net (code "20") (name "MOSI") (class "Default")
      (node (ref "D11") (pin "1") (pinfunction "1_1") (pintype "passive"))
      (node (ref "J1") (pin "14") (pinfunction "14_14") (pintype "bidirectional"))
      (node (ref "J4") (pin "P3") (pinfunction "CMD_P3") (pintype "bidirectional"))
      (node (ref "R6") (pin "1") (pinfunction "1_1") (pintype "passive"))
      (node (ref "TP7") (pin "TP") (pinfunction "TP_TP") (pintype "input"))
      (node (ref "U1") (pin "5") (pinfunction "DI(IO0)_5") (pintype "bidirectional"))
      (node (ref "U2") (pin "7") (pinfunction "IO7_7") (pintype "bidirectional"))
    )
    (net (code "21") (name "Net-(CHG_LED-PadC)") (class "Default")
      (node (ref "CHG_LED") (pin "C") (pinfunction "C_C") (pintype "passive"))
      (node (ref "R1_BAT") (pin "1") (pinfunction "1_1") (pintype "passive"))
    )
    (net (code "22") (name "Net-(D2-CATHODE)") (class "Default")
      (node (ref "C1_BAT1") (pin "1") (pinfunction "1_1") (pintype "passive"))
      (node (ref "D2") (pin "2") (pinfunction "CATHODE_2") (pintype "bidirectional"))
      (node (ref "IC4") (pin "1") (pinfunction "VIN_1") (pintype "bidirectional"))
      (node (ref "IC4") (pin "3") (pinfunction "CE_3") (pintype "bidirectional"))
      (node (ref "Q1") (pin "3") (pinfunction "S_3") (pintype "bidirectional"))
    )
    (net (code "23") (name "Net-(D3-A)") (class "Default")
      (node (ref "C1") (pin "1") (pinfunction "1_1") (pintype "passive"))
      (node (ref "D3") (pin "1") (pinfunction "A_1") (pintype "bidirectional"))
      (node (ref "D4") (pin "2") (pinfunction "K_2") (pintype "bidirectional"))
    )
    (net (code "24") (name "Net-(D7-CATHODE)") (class "Default")
      (node (ref "D7") (pin "2") (pinfunction "CATHODE_2") (pintype "bidirectional"))
      (node (ref "R_CAPACITOR") (pin "1") (pinfunction "1_1") (pintype "passive"))
    )
    (net (code "25") (name "Net-(EPD_C1-Pad1)") (class "Default")
      (node (ref "EPD_C1") (pin "1") (pinfunction "1_1") (pintype "passive"))
      (node (ref "J1") (pin "4") (pinfunction "4_4") (pintype "bidirectional"))
    )
    (net (code "26") (name "Net-(EPD_C2-Pad1)") (class "Default")
      (node (ref "EPD_C2") (pin "1") (pinfunction "1_1") (pintype "passive"))
      (node (ref "J1") (pin "5") (pinfunction "5_5") (pintype "bidirectional"))
    )
    (net (code "27") (name "Net-(EPD_C6-Pad1)") (class "Default")
      (node (ref "EPD_C6") (pin "1") (pinfunction "1_1") (pintype "passive"))
      (node (ref "J1") (pin "18") (pinfunction "18_18") (pintype "bidirectional"))
    )
    (net (code "28") (name "Net-(EPD_C7-Pad1)") (class "Default")
      (node (ref "EPD_C7") (pin "1") (pinfunction "1_1") (pintype "passive"))
      (node (ref "J1") (pin "19") (pinfunction "19_19") (pintype "bidirectional"))
    )
    (net (code "29") (name "Net-(EPD_C8-Pad1)") (class "Default")
      (node (ref "EPD_C8") (pin "1") (pinfunction "1_1") (pintype "passive"))
      (node (ref "J1") (pin "20") (pinfunction "20_20") (pintype "bidirectional"))
    )
    (net (code "30") (name "Net-(EPD_C10-Pad1)") (class "Default")
      (node (ref "EPD_C10") (pin "1") (pinfunction "1_1") (pintype "passive"))
      (node (ref "J1") (pin "22") (pinfunction "22_22") (pintype "bidirectional"))
    )
    (net (code "31") (name "Net-(EPD_C12-Pad1)") (class "Default")
      (node (ref "EPD_C12") (pin "1") (pinfunction "1_1") (pintype "passive"))
      (node (ref "J1") (pin "24") (pinfunction "24_24") (pintype "bidirectional"))
    )
    (net (code "32") (name "Net-(IC1-CT)") (class "Default")
      (node (ref "C_DELAY") (pin "1") (pinfunction "1_1") (pintype "passive"))
      (node (ref "IC1") (pin "5") (pinfunction "CT_5") (pintype "bidirectional"))
    )
    (net (code "33") (name "Net-(J2-PadA5)") (class "Default")
      (node (ref "J2") (pin "A5") (pinfunction "A5_A5") (pintype "bidirectional"))
      (node (ref "R_J2") (pin "2") (pinfunction "2_2") (pintype "passive"))
    )
    (net (code "34") (name "Net-(J2-PadB5)") (class "Default")
      (node (ref "J2") (pin "B5") (pinfunction "B5_B5") (pintype "bidirectional"))
      (node (ref "R2-USB") (pin "1") (pinfunction "1_1") (pintype "passive"))
    )
    (net (code "35") (name "Net-(MCP73831-PROG)") (class "Default")
      (node (ref "MCP73831") (pin "5") (pinfunction "PROG_5") (pintype "input"))
      (node (ref "R2_BAT") (pin "2") (pinfunction "2_2") (pintype "passive"))
    )
    (net (code "36") (name "Net-(MCP73831-STAT)") (class "Default")
      (node (ref "MCP73831") (pin "1") (pinfunction "STAT_1") (pintype "output"))
      (node (ref "R1_BAT") (pin "2") (pinfunction "2_2") (pintype "passive"))
    )
    (net (code "37") (name "PREVGH") (class "Default")
      (node (ref "D5") (pin "2") (pinfunction "K_2") (pintype "bidirectional"))
      (node (ref "EPD_C9") (pin "1") (pinfunction "1_1") (pintype "passive"))
      (node (ref "J1") (pin "21") (pinfunction "21_21") (pintype "bidirectional"))
    )
    (net (code "38") (name "PREVGL") (class "Default")
      (node (ref "D4") (pin "1") (pinfunction "A_1") (pintype "bidirectional"))
      (node (ref "EPD_C11") (pin "1") (pinfunction "1_1") (pintype "passive"))
      (node (ref "J1") (pin "23") (pinfunction "23_23") (pintype "bidirectional"))
    )
    (net (code "39") (name "RESE") (class "Default")
      (node (ref "J1") (pin "3") (pinfunction "3_3") (pintype "bidirectional"))
      (node (ref "Q3") (pin "2") (pinfunction "S_2") (pintype "bidirectional"))
      (node (ref "R3") (pin "2") (pinfunction "2_2") (pintype "passive"))
    )
    (net (code "40") (name "RESE'") (class "Default")
      (node (ref "R2") (pin "2") (pinfunction "2_2") (pintype "passive"))
      (node (ref "R3") (pin "1") (pinfunction "1_1") (pintype "passive"))
      (node (ref "SJ1") (pin "2") (pinfunction "2_2") (pintype "passive"))
    )
    (net (code "41") (name "RESET") (class "Default")
      (node (ref "C5") (pin "1") (pinfunction "1_1") (pintype "passive"))
      (node (ref "IC1") (pin "1") (pinfunction "VOUT_1") (pintype "bidirectional"))
      (node (ref "R_RESET") (pin "1") (pinfunction "1_1") (pintype "passive"))
      (node (ref "U$1") (pin "3") (pinfunction "3_3") (pintype "passive"))
      (node (ref "U$1") (pin "4") (pinfunction "4_4") (pintype "passive"))
      (node (ref "U2") (pin "3") (pinfunction "EN_3") (pintype "input"))
    )
    (net (code "42") (name "RTC_RST") (class "Default")
      (node (ref "U2") (pin "16") (pinfunction "IO18_16") (pintype "bidirectional"))
      (node (ref "U3") (pin "4") (pinfunction "~{RST}_4") (pintype "input"))
    )
    (net (code "43") (name "RX") (class "Default")
      (node (ref "TP2") (pin "TP") (pinfunction "TP_TP") (pintype "input"))
      (node (ref "U2") (pin "24") (pinfunction "RXD0/GPIO17_24") (pintype "bidirectional"))
    )
    (net (code "44") (name "SCK") (class "Default")
      (node (ref "D10") (pin "1") (pinfunction "1_1") (pintype "passive"))
      (node (ref "J1") (pin "13") (pinfunction "13_13") (pintype "bidirectional"))
      (node (ref "J4") (pin "P5") (pinfunction "CLK_P5") (pintype "bidirectional"))
      (node (ref "R7") (pin "1") (pinfunction "1_1") (pintype "passive"))
      (node (ref "TP8") (pin "TP") (pinfunction "TP_TP") (pintype "input"))
      (node (ref "U1") (pin "6") (pinfunction "CLK_6") (pintype "input"))
      (node (ref "U2") (pin "6") (pinfunction "IO6_6") (pintype "bidirectional"))
    )
    (net (code "45") (name "SCL") (class "Default")
      (node (ref "J3") (pin "4") (pinfunction "4_4") (pintype "passive"))
      (node (ref "R2-PINH") (pin "1") (pinfunction "1_1") (pintype "passive"))
      (node (ref "SENSOR2") (pin "4") (pinfunction "SCK_4") (pintype "input"))
      (node (ref "U2") (pin "20") (pinfunction "IO22_20") (pintype "bidirectional"))
      (node (ref "U3") (pin "16") (pinfunction "SCL_16") (pintype "input"))
      (node (ref "U4") (pin "7") (pinfunction "SCL_7") (pintype "input"))
    )
    (net (code "46") (name "SDA") (class "Default")
      (node (ref "J3") (pin "3") (pinfunction "3_3") (pintype "passive"))
      (node (ref "R1-PINH") (pin "1") (pinfunction "1_1") (pintype "passive"))
      (node (ref "SENSOR2") (pin "3") (pinfunction "SDI_3") (pintype "bidirectional"))
      (node (ref "U2") (pin "19") (pinfunction "IO21_19") (pintype "bidirectional"))
      (node (ref "U3") (pin "15") (pinfunction "SDA_15") (pintype "bidirectional"))
      (node (ref "U4") (pin "8") (pinfunction "SDA_8") (pintype "bidirectional"))
    )
    (net (code "47") (name "SRC") (class "Default")
      (node (ref "C1") (pin "2") (pinfunction "2_2") (pintype "passive"))
      (node (ref "D5") (pin "1") (pinfunction "A_1") (pintype "bidirectional"))
      (node (ref "L1") (pin "1") (pinfunction "1_1") (pintype "passive"))
      (node (ref "Q3") (pin "3") (pinfunction "D_3") (pintype "bidirectional"))
    )
    (net (code "48") (name "SS_SD") (class "Default")
      (node (ref "D8") (pin "1") (pinfunction "1_1") (pintype "passive"))
      (node (ref "J4") (pin "P2") (pinfunction "CD/DAT3_P2") (pintype "bidirectional"))
      (node (ref "R10") (pin "1") (pinfunction "1_1") (pintype "passive"))
      (node (ref "U2") (pin "4") (pinfunction "IO4_4") (pintype "bidirectional"))
    )
    (net (code "49") (name "TX") (class "Default")
      (node (ref "TP1") (pin "TP") (pinfunction "TP_TP") (pintype "input"))
      (node (ref "U2") (pin "25") (pinfunction "TXD0/GPIO16_25") (pintype "bidirectional"))
    )
    (net (code "50") (name "USB_D+") (class "Default")
      (node (ref "D1") (pin "1") (pinfunction "I/O1_1_1") (pintype "bidirectional"))
      (node (ref "U2") (pin "14") (pinfunction "IO13_14") (pintype "bidirectional"))
    )
    (net (code "51") (name "USB_D-") (class "Default")
      (node (ref "D1") (pin "3") (pinfunction "I/O2_1_3") (pintype "bidirectional"))
      (node (ref "U2") (pin "13") (pinfunction "IO12_13") (pintype "bidirectional"))
    )
    (net (code "52") (name "VBAT") (class "Default")
      (node (ref "C2_BAT") (pin "1") (pinfunction "1_1") (pintype "passive"))
      (node (ref "MCP73831") (pin "3") (pinfunction "VBAT_3") (pintype "power_in"))
      (node (ref "Q1") (pin "1") (pinfunction "D_1") (pintype "bidirectional"))
      (node (ref "TP3") (pin "TP") (pinfunction "TP_TP") (pintype "input"))
      (node (ref "U4") (pin "2") (pinfunction "CELL_2") (pintype "power_in"))
      (node (ref "U4") (pin "3") (pinfunction "VDD_3") (pintype "power_in"))
    )
    (net (code "53") (name "VBUS") (class "Default")
      (node (ref "C1_BAT") (pin "1") (pinfunction "1_1") (pintype "passive"))
      (node (ref "C4_USB") (pin "1") (pinfunction "1_1") (pintype "passive"))
      (node (ref "C5_USB") (pin "1") (pinfunction "1_1") (pintype "passive"))
      (node (ref "CHG_LED") (pin "A") (pinfunction "A_A") (pintype "passive"))
      (node (ref "D1") (pin "5") (pinfunction "VBUS_5") (pintype "bidirectional"))
      (node (ref "D2") (pin "1") (pinfunction "ANODE_1") (pintype "bidirectional"))
      (node (ref "MCP73831") (pin "4") (pinfunction "VIN_4") (pintype "power_in"))
      (node (ref "PFMF.050.1") (pin "2") (pinfunction "2_2") (pintype "passive"))
      (node (ref "Q1") (pin "2") (pinfunction "G_2") (pintype "bidirectional"))
      (node (ref "R1_PWRUSB") (pin "2") (pinfunction "2_2") (pintype "passive"))
      (node (ref "TP14") (pin "TP") (pinfunction "TP_TP") (pintype "input"))
    )
    (net (code "54") (name "VRTC") (class "Default")
      (node (ref "C10") (pin "1") (pinfunction "1_1") (pintype "passive"))
      (node (ref "C10_SUPERCAP") (pin "2") (pinfunction "2_2") (pintype "passive"))
      (node (ref "R_CAPACITOR") (pin "2") (pinfunction "2_2") (pintype "passive"))
      (node (ref "U3") (pin "14") (pinfunction "VBAT_14") (pintype "power_in"))
    )
    (net (code "55") (name "VUSB") (class "Default")
      (node (ref "J2") (pin "A4") (pinfunction "A4_A4") (pintype "bidirectional"))
      (node (ref "J2") (pin "A9") (pinfunction "A9_A9") (pintype "bidirectional"))
      (node (ref "J2") (pin "B4") (pinfunction "B4_B4") (pintype "bidirectional"))
      (node (ref "J2") (pin "B9") (pinfunction "B9_B9") (pintype "bidirectional"))
      (node (ref "PFMF.050.1") (pin "1") (pinfunction "1_1") (pintype "passive"))
    )
    (net (code "56") (name "unconnected-(IC1-NC-Pad4)") (class "Default")
      (node (ref "IC1") (pin "4") (pinfunction "NC_4") (pintype "no_connect"))
    )
    (net (code "57") (name "unconnected-(IC4-NC-Pad4)") (class "Default")
      (node (ref "IC4") (pin "4") (pinfunction "NC_4") (pintype "no_connect"))
    )
    (net (code "58") (name "unconnected-(J1-Pad1)") (class "Default")
      (node (ref "J1") (pin "1") (pinfunction "1_1") (pintype "bidirectional"))
    )
    (net (code "59") (name "unconnected-(J1-Pad6)") (class "Default")
      (node (ref "J1") (pin "6") (pinfunction "6_6") (pintype "bidirectional"))
    )
    (net (code "60") (name "unconnected-(J1-Pad7)") (class "Default")
      (node (ref "J1") (pin "7") (pinfunction "7_7") (pintype "bidirectional"))
    )
    (net (code "61") (name "unconnected-(J2-PadA8)") (class "Default")
      (node (ref "J2") (pin "A8") (pinfunction "A8_A8") (pintype "bidirectional"))
    )
    (net (code "62") (name "unconnected-(J2-PadB8)") (class "Default")
      (node (ref "J2") (pin "B8") (pinfunction "B8_B8") (pintype "bidirectional"))
    )
    (net (code "63") (name "unconnected-(J4-DAT1-PadP8)") (class "Default")
      (node (ref "J4") (pin "P8") (pinfunction "DAT1_P8") (pintype "bidirectional"))
    )
    (net (code "64") (name "unconnected-(J4-DAT2-PadP1)") (class "Default")
      (node (ref "J4") (pin "P1") (pinfunction "DAT2_P1") (pintype "bidirectional"))
    )
    (net (code "65") (name "unconnected-(J4-DETECTION_1-PadS1)") (class "Default")
      (node (ref "J4") (pin "S1") (pinfunction "DETECTION_1_S1") (pintype "bidirectional"))
    )
    (net (code "66") (name "unconnected-(J4-DETECTION_2-PadS2)") (class "Default")
      (node (ref "J4") (pin "S2") (pinfunction "DETECTION_2_S2") (pintype "bidirectional"))
    )
    (net (code "67") (name "unconnected-(U2-NC-Pad22)") (class "Default")
      (node (ref "U2") (pin "22") (pinfunction "NC_22") (pintype "no_connect"))
    )
    (net (code "68") (name "unconnected-(U4-~{ALERT}-Pad5)") (class "Default")
      (node (ref "U4") (pin "5") (pinfunction "~{ALERT}_5") (pintype "output"))
    )
  )
)
